# 5V-3V3_Reg_Board.net
KiCad netlist of a schematic drawn in EAGLE
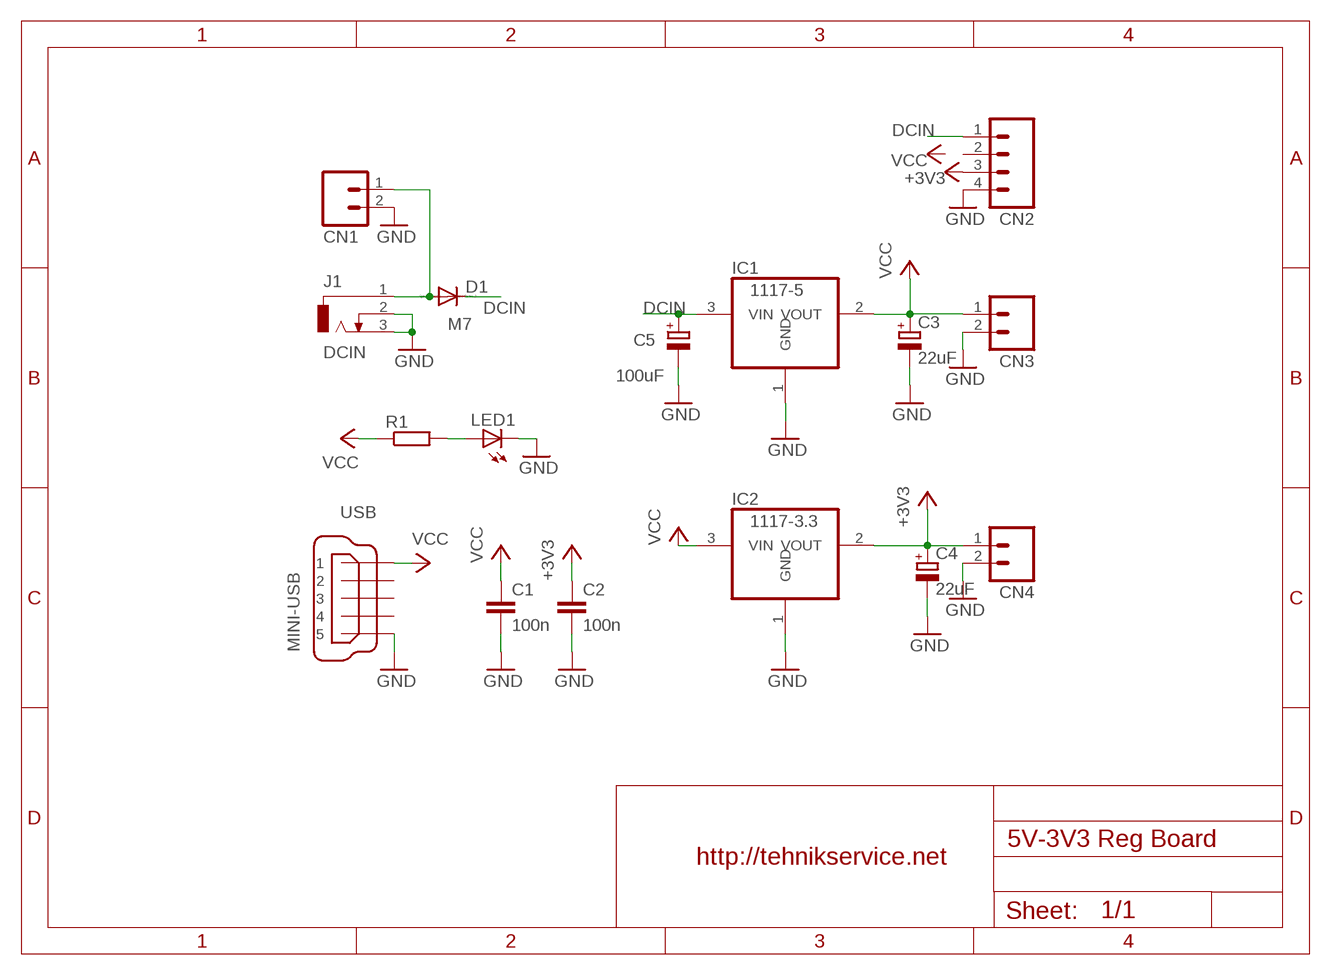
[diagram p0: schematic, sheet 1]

(export (version "E")
  (design (tool "Eeschema 10.0.6"))
  (components
    (comp (ref "C1")
      (value "100n")
      (footprint "eagle-import:C0805")
      (libsource (lib "eagle-import") (part "C-EUC0805"))
    )
    (comp (ref "C2")
      (value "100n")
      (footprint "eagle-import:C0805")
      (libsource (lib "eagle-import") (part "C-EUC0805"))
    )
    (comp (ref "C3")
      (value "22uF")
      (footprint "eagle-import:E2,5-5")
      (libsource (lib "eagle-import") (part "CPOL-EUE2.5-5"))
    )
    (comp (ref "C4")
      (value "22uF")
      (footprint "eagle-import:E2,5-5")
      (libsource (lib "eagle-import") (part "CPOL-EUE2.5-5"))
    )
    (comp (ref "C5")
      (value "100uF")
      (footprint "eagle-import:E2,5-5")
      (libsource (lib "eagle-import") (part "CPOL-EUE2.5-5"))
    )
    (comp (ref "CN1")
      (value "M02")
      (footprint "eagle-import:02P")
      (libsource (lib "eagle-import") (part "M02"))
    )
    (comp (ref "CN2")
      (value "M04")
      (footprint "eagle-import:04P")
      (libsource (lib "eagle-import") (part "M04"))
    )
    (comp (ref "CN3")
      (value "M02")
      (footprint "eagle-import:02P")
      (libsource (lib "eagle-import") (part "M02"))
    )
    (comp (ref "CN4")
      (value "M02")
      (footprint "eagle-import:02P")
      (libsource (lib "eagle-import") (part "M02"))
    )
    (comp (ref "D1")
      (value "M7")
      (footprint "eagle-import:DO-214AC")
      (libsource (lib "eagle-import") (part "DIODE-DO-214AC"))
    )
    (comp (ref "IC1")
      (value "1117-5")
      (footprint "eagle-import:SOT223")
      (fields (field (name "MPN") "REG1117"))
      (libsource (lib "eagle-import") (part "REG1117"))
    )
    (comp (ref "IC2")
      (value "1117-3.3")
      (footprint "eagle-import:SOT223")
      (fields (field (name "MPN") "REG1117"))
      (libsource (lib "eagle-import") (part "REG1117"))
    )
    (comp (ref "J1")
      (value "DCIN")
      (footprint "eagle-import:DCJ0202")
      (libsource (lib "eagle-import") (part "DCJ0202"))
    )
    (comp (ref "LED1")
      (value "LEDCHIPLED_0805")
      (footprint "eagle-import:CHIPLED_0805")
      (libsource (lib "eagle-import") (part "LEDCHIPLED_0805"))
    )
    (comp (ref "R1")
      (value "R-EU_R0805")
      (footprint "eagle-import:R0805")
      (libsource (lib "eagle-import") (part "R-EU_R0805"))
    )
    (comp (ref "USB")
      (value "MINI-USB")
      (footprint "eagle-import:32005-201")
      (libsource (lib "eagle-import") (part "MINI-USB-32005-201"))
    )
  )
  (nets
    (net (code "1") (name "+3V3") (class "Default")
      (node (ref "C2") (pin "1") (pinfunction "1_1") (pintype "passive"))
      (node (ref "C4") (pin "+") (pinfunction "+_+") (pintype "passive"))
      (node (ref "CN2") (pin "3") (pinfunction "3_3") (pintype "passive"))
      (node (ref "CN4") (pin "1") (pinfunction "1_1") (pintype "passive"))
      (node (ref "IC2") (pin "2") (pinfunction "VOUT_2") (pintype "output"))
    )
    (net (code "2") (name "/DCIN") (class "Default")
      (node (ref "C5") (pin "+") (pinfunction "+_+") (pintype "passive"))
      (node (ref "CN2") (pin "1") (pinfunction "1_1") (pintype "passive"))
      (node (ref "D1") (pin "C") (pinfunction "C_C") (pintype "passive"))
      (node (ref "IC1") (pin "3") (pinfunction "VIN_3") (pintype "input"))
    )
    (net (code "3") (name "GND") (class "Default")
      (node (ref "C1") (pin "2") (pinfunction "2_2") (pintype "passive"))
      (node (ref "C2") (pin "2") (pinfunction "2_2") (pintype "passive"))
      (node (ref "C3") (pin "-") (pinfunction "-_-") (pintype "passive"))
      (node (ref "C4") (pin "-") (pinfunction "-_-") (pintype "passive"))
      (node (ref "C5") (pin "-") (pinfunction "-_-") (pintype "passive"))
      (node (ref "CN1") (pin "2") (pinfunction "2_2") (pintype "passive"))
      (node (ref "CN2") (pin "4") (pinfunction "4_4") (pintype "passive"))
      (node (ref "CN3") (pin "2") (pinfunction "2_2") (pintype "passive"))
      (node (ref "CN4") (pin "2") (pinfunction "2_2") (pintype "passive"))
      (node (ref "IC1") (pin "1") (pinfunction "GND_1") (pintype "power_in"))
      (node (ref "IC2") (pin "1") (pinfunction "GND_1") (pintype "power_in"))
      (node (ref "J1") (pin "2") (pinfunction "2_2") (pintype "passive"))
      (node (ref "J1") (pin "3") (pinfunction "3_3") (pintype "passive"))
      (node (ref "LED1") (pin "C") (pinfunction "C_C") (pintype "passive"))
      (node (ref "USB") (pin "5") (pinfunction "5_5") (pintype "passive"))
    )
    (net (code "4") (name "Net-(CN1-Pad1)") (class "Default")
      (node (ref "CN1") (pin "1") (pinfunction "1_1") (pintype "passive"))
      (node (ref "D1") (pin "A") (pinfunction "A_A") (pintype "passive"))
      (node (ref "J1") (pin "1") (pinfunction "1_1") (pintype "passive"))
    )
    (net (code "5") (name "Net-(LED1-PadA)") (class "Default")
      (node (ref "LED1") (pin "A") (pinfunction "A_A") (pintype "passive"))
      (node (ref "R1") (pin "2") (pinfunction "2_2") (pintype "passive"))
    )
    (net (code "6") (name "VCC") (class "Default")
      (node (ref "C1") (pin "1") (pinfunction "1_1") (pintype "passive"))
      (node (ref "C3") (pin "+") (pinfunction "+_+") (pintype "passive"))
      (node (ref "CN3") (pin "1") (pinfunction "1_1") (pintype "passive"))
      (node (ref "IC1") (pin "2") (pinfunction "VOUT_2") (pintype "output"))
      (node (ref "IC2") (pin "3") (pinfunction "VIN_3") (pintype "input"))
      (node (ref "R1") (pin "1") (pinfunction "1_1") (pintype "passive"))
      (node (ref "USB") (pin "1") (pinfunction "1_1") (pintype "passive"))
    )
    (net (code "7") (name "unconnected-(CN2-Pad2)") (class "Default")
      (node (ref "CN2") (pin "2") (pinfunction "2_2") (pintype "passive"))
    )
    (net (code "8") (name "unconnected-(USB-Pad2)") (class "Default")
      (node (ref "USB") (pin "2") (pinfunction "2_2") (pintype "passive"))
    )
    (net (code "9") (name "unconnected-(USB-Pad3)") (class "Default")
      (node (ref "USB") (pin "3") (pinfunction "3_3") (pintype "passive"))
    )
    (net (code "10") (name "unconnected-(USB-Pad4)") (class "Default")
      (node (ref "USB") (pin "4") (pinfunction "4_4") (pintype "passive"))
    )
  )
)
